# expansion_module_spi_flash.net
KiCad netlist of a schematic drawn in EAGLE
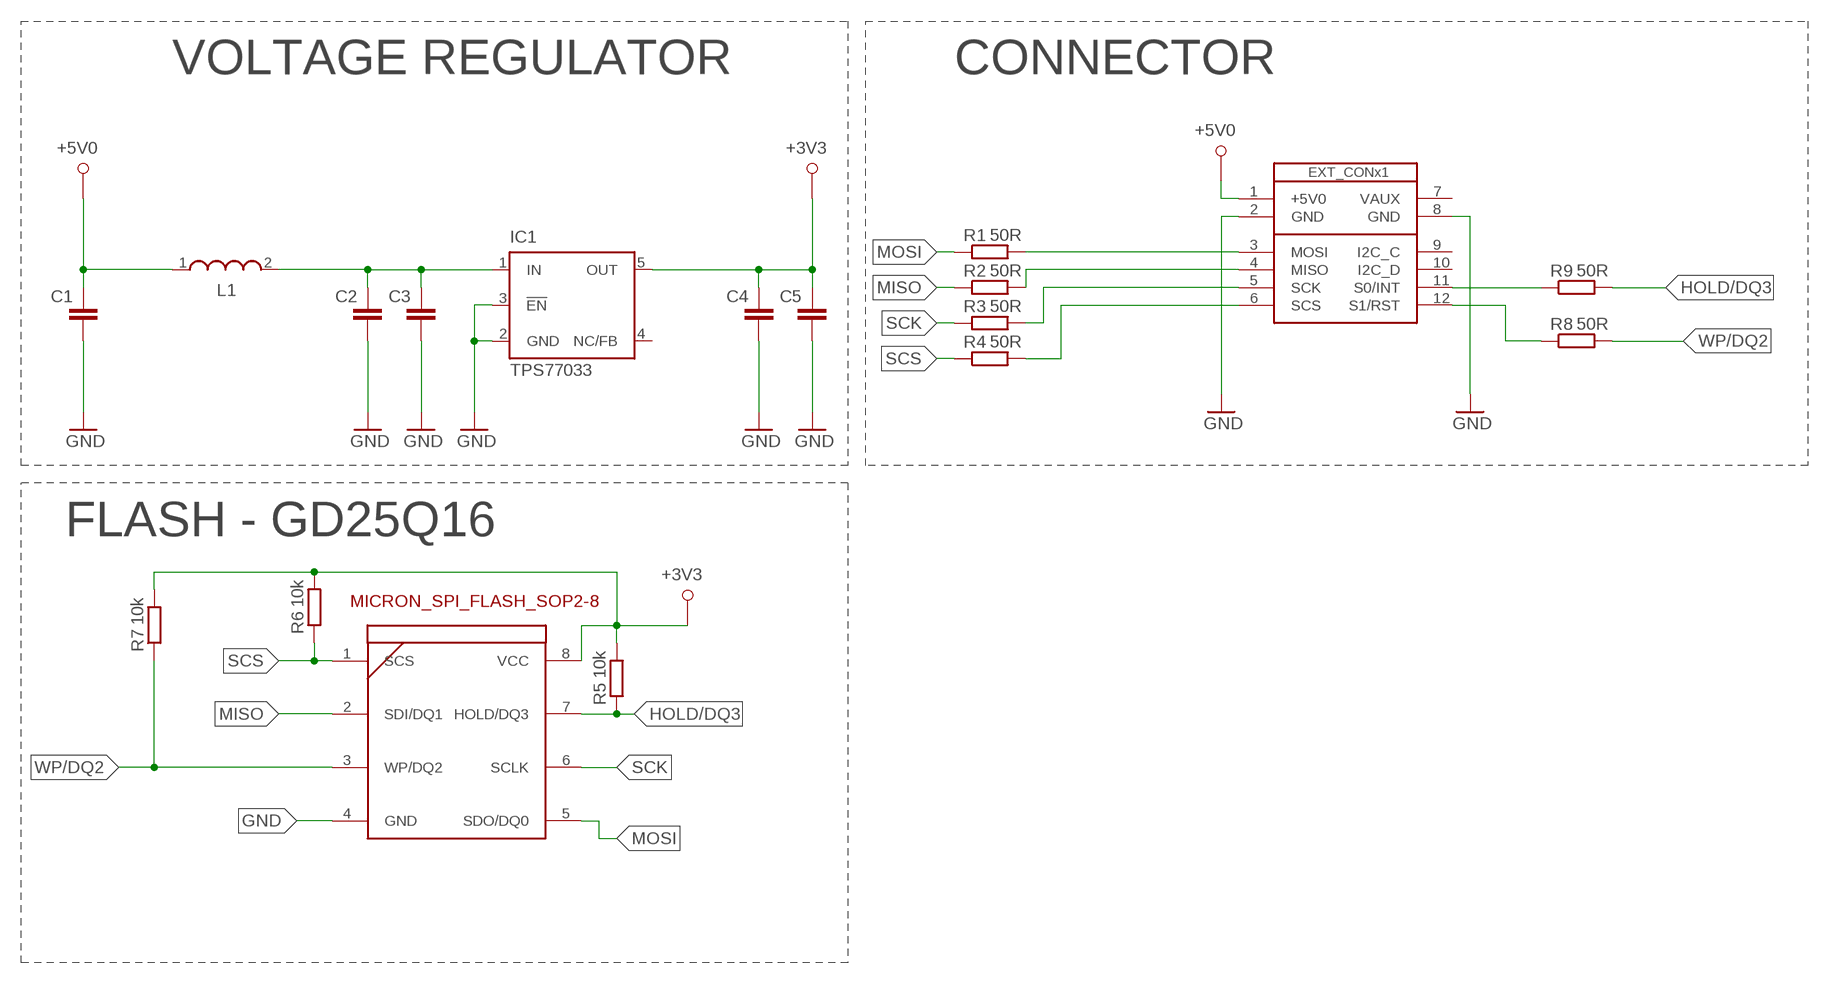
[diagram p0: schematic, sheet 1]

(export (version "E")
  (design (tool "Eeschema 10.0.6"))
  (components
    (comp (ref "C1")
      (value "C-EUC0805")
      (footprint "eagle-import:C0805")
      (libsource (lib "eagle-import") (part "C-EUC0805"))
    )
    (comp (ref "C2")
      (value "C-EUC0805")
      (footprint "eagle-import:C0805")
      (libsource (lib "eagle-import") (part "C-EUC0805"))
    )
    (comp (ref "C3")
      (value "C-EUC0805")
      (footprint "eagle-import:C0805")
      (libsource (lib "eagle-import") (part "C-EUC0805"))
    )
    (comp (ref "C4")
      (value "C-EUC0805")
      (footprint "eagle-import:C0805")
      (libsource (lib "eagle-import") (part "C-EUC0805"))
    )
    (comp (ref "C5")
      (value "C-EUC0805")
      (footprint "eagle-import:C0805")
      (libsource (lib "eagle-import") (part "C-EUC0805"))
    )
    (comp (ref "IC1")
      (value "TPS77033")
      (footprint "eagle-import:SOT23-DBV")
      (fields (field (name "MF") "TEXAS INSTRUMENTS") (field (name "MPN") "TPS77033DBVT"))
      (libsource (lib "eagle-import") (part "TPS77033"))
    )
    (comp (ref "L1")
      (value "WE-LQ_1210")
      (footprint "eagle-import:WE-LQ_M")
      (libsource (lib "eagle-import") (part "WE-LQ_1210"))
    )
    (comp (ref "R1")
      (value "50R")
      (footprint "eagle-import:R0805")
      (libsource (lib "eagle-import") (part "R-EU_R0805"))
    )
    (comp (ref "R2")
      (value "50R")
      (footprint "eagle-import:R0805")
      (libsource (lib "eagle-import") (part "R-EU_R0805"))
    )
    (comp (ref "R3")
      (value "50R")
      (footprint "eagle-import:R0805")
      (libsource (lib "eagle-import") (part "R-EU_R0805"))
    )
    (comp (ref "R4")
      (value "50R")
      (footprint "eagle-import:R0805")
      (libsource (lib "eagle-import") (part "R-EU_R0805"))
    )
    (comp (ref "R5")
      (value "10k")
      (footprint "eagle-import:R0805")
      (libsource (lib "eagle-import") (part "R-EU_R0805"))
    )
    (comp (ref "R6")
      (value "10k")
      (footprint "eagle-import:R0805")
      (libsource (lib "eagle-import") (part "R-EU_R0805"))
    )
    (comp (ref "R7")
      (value "10k")
      (footprint "eagle-import:R0805")
      (libsource (lib "eagle-import") (part "R-EU_R0805"))
    )
    (comp (ref "R8")
      (value "50R")
      (footprint "eagle-import:R0805")
      (libsource (lib "eagle-import") (part "R-EU_R0805"))
    )
    (comp (ref "R9")
      (value "50R")
      (footprint "eagle-import:R0805")
      (libsource (lib "eagle-import") (part "R-EU_R0805"))
    )
    (comp (ref "U$1")
      (value "SB_EXT_CON_X1_SPI")
      (footprint "eagle-import:SB_EXT_CON_X1_FULL")
      (libsource (lib "eagle-import") (part "SB_EXT_CON_X1_SPI"))
    )
    (comp (ref "U$11")
      (value "MICRON_SPI_FLASH")
      (footprint "eagle-import:SO-08M")
      (libsource (lib "eagle-import") (part "MICRON_SPI_FLASH"))
    )
  )
  (nets
    (net (code "1") (name "+3V3") (class "Default")
      (node (ref "C4") (pin "2") (pinfunction "2_2") (pintype "passive"))
      (node (ref "C5") (pin "2") (pinfunction "2_2") (pintype "passive"))
      (node (ref "IC1") (pin "5") (pinfunction "OUT_5") (pintype "passive"))
      (node (ref "R5") (pin "2") (pinfunction "2_2") (pintype "passive"))
      (node (ref "R6") (pin "2") (pinfunction "2_2") (pintype "passive"))
      (node (ref "R7") (pin "2") (pinfunction "2_2") (pintype "passive"))
      (node (ref "U$11") (pin "8") (pinfunction "VCC_8") (pintype "bidirectional"))
    )
    (net (code "2") (name "+5V0") (class "Default")
      (node (ref "C1") (pin "2") (pinfunction "2_2") (pintype "passive"))
      (node (ref "L1") (pin "1") (pinfunction "1_1") (pintype "passive"))
      (node (ref "U$1") (pin "1") (pinfunction "+5V0_1") (pintype "bidirectional"))
    )
    (net (code "3") (name "GND") (class "Default")
      (node (ref "C1") (pin "1") (pinfunction "1_1") (pintype "passive"))
      (node (ref "C2") (pin "1") (pinfunction "1_1") (pintype "passive"))
      (node (ref "C3") (pin "1") (pinfunction "1_1") (pintype "passive"))
      (node (ref "C4") (pin "1") (pinfunction "1_1") (pintype "passive"))
      (node (ref "C5") (pin "1") (pinfunction "1_1") (pintype "passive"))
      (node (ref "IC1") (pin "2") (pinfunction "GND_2") (pintype "power_in"))
      (node (ref "IC1") (pin "3") (pinfunction "~{EN}_3") (pintype "input"))
      (node (ref "U$1") (pin "2") (pinfunction "GND_2") (pintype "bidirectional"))
      (node (ref "U$1") (pin "8") (pinfunction "GND_8") (pintype "bidirectional"))
      (node (ref "U$11") (pin "4") (pinfunction "GND_4") (pintype "bidirectional"))
    )
    (net (code "4") (name "HOLD{slash}DQ3") (class "Default")
      (node (ref "R5") (pin "1") (pinfunction "1_1") (pintype "passive"))
      (node (ref "R9") (pin "2") (pinfunction "2_2") (pintype "passive"))
      (node (ref "U$11") (pin "7") (pinfunction "HOLD/DQ3_7") (pintype "bidirectional"))
    )
    (net (code "5") (name "MISO") (class "Default")
      (node (ref "R2") (pin "1") (pinfunction "1_1") (pintype "passive"))
      (node (ref "U$11") (pin "2") (pinfunction "SDI/DQ1_2") (pintype "bidirectional"))
    )
    (net (code "6") (name "MOSI") (class "Default")
      (node (ref "R1") (pin "1") (pinfunction "1_1") (pintype "passive"))
      (node (ref "U$11") (pin "5") (pinfunction "SDO/DQ0_5") (pintype "bidirectional"))
    )
    (net (code "7") (name "Net-(IC1-IN)") (class "Default")
      (node (ref "C2") (pin "2") (pinfunction "2_2") (pintype "passive"))
      (node (ref "C3") (pin "2") (pinfunction "2_2") (pintype "passive"))
      (node (ref "IC1") (pin "1") (pinfunction "IN_1") (pintype "input"))
      (node (ref "L1") (pin "2") (pinfunction "2_2") (pintype "passive"))
    )
    (net (code "8") (name "Net-(U$1-MISO)") (class "Default")
      (node (ref "R2") (pin "2") (pinfunction "2_2") (pintype "passive"))
      (node (ref "U$1") (pin "4") (pinfunction "MISO_4") (pintype "bidirectional"))
    )
    (net (code "9") (name "Net-(U$1-MOSI)") (class "Default")
      (node (ref "R1") (pin "2") (pinfunction "2_2") (pintype "passive"))
      (node (ref "U$1") (pin "3") (pinfunction "MOSI_3") (pintype "bidirectional"))
    )
    (net (code "10") (name "Net-(U$1-S0{slash}INT)") (class "Default")
      (node (ref "R9") (pin "1") (pinfunction "1_1") (pintype "passive"))
      (node (ref "U$1") (pin "11") (pinfunction "S0/INT_11") (pintype "bidirectional"))
    )
    (net (code "11") (name "Net-(U$1-S1{slash}RST)") (class "Default")
      (node (ref "R8") (pin "1") (pinfunction "1_1") (pintype "passive"))
      (node (ref "U$1") (pin "12") (pinfunction "S1/RST_12") (pintype "bidirectional"))
    )
    (net (code "12") (name "Net-(U$1-SCK)") (class "Default")
      (node (ref "R3") (pin "2") (pinfunction "2_2") (pintype "passive"))
      (node (ref "U$1") (pin "5") (pinfunction "SCK_5") (pintype "bidirectional"))
    )
    (net (code "13") (name "Net-(U$1-SCS)") (class "Default")
      (node (ref "R4") (pin "2") (pinfunction "2_2") (pintype "passive"))
      (node (ref "U$1") (pin "6") (pinfunction "SCS_6") (pintype "bidirectional"))
    )
    (net (code "14") (name "SCK") (class "Default")
      (node (ref "R3") (pin "1") (pinfunction "1_1") (pintype "passive"))
      (node (ref "U$11") (pin "6") (pinfunction "SCLK_6") (pintype "bidirectional"))
    )
    (net (code "15") (name "SCS") (class "Default")
      (node (ref "R4") (pin "1") (pinfunction "1_1") (pintype "passive"))
      (node (ref "R6") (pin "1") (pinfunction "1_1") (pintype "passive"))
      (node (ref "U$11") (pin "1") (pinfunction "SCS_1") (pintype "bidirectional"))
    )
    (net (code "16") (name "WP{slash}DQ2") (class "Default")
      (node (ref "R7") (pin "1") (pinfunction "1_1") (pintype "passive"))
      (node (ref "R8") (pin "2") (pinfunction "2_2") (pintype "passive"))
      (node (ref "U$11") (pin "3") (pinfunction "WP/DQ2_3") (pintype "bidirectional"))
    )
    (net (code "17") (name "unconnected-(IC1-NC{slash}FB-Pad4)") (class "Default")
      (node (ref "IC1") (pin "4") (pinfunction "NC/FB_4") (pintype "passive"))
    )
    (net (code "18") (name "unconnected-(U$1-I2C_C-Pad9)") (class "Default")
      (node (ref "U$1") (pin "9") (pinfunction "I2C_C_9") (pintype "bidirectional"))
    )
    (net (code "19") (name "unconnected-(U$1-I2C_D-Pad10)") (class "Default")
      (node (ref "U$1") (pin "10") (pinfunction "I2C_D_10") (pintype "bidirectional"))
    )
    (net (code "20") (name "unconnected-(U$1-VAUX-Pad7)") (class "Default")
      (node (ref "U$1") (pin "7") (pinfunction "VAUX_7") (pintype "bidirectional"))
    )
  )
)
